# Simple-Charger-LiIon-OpampBased-LM324-al.net
KiCad netlist of a schematic drawn in EAGLE
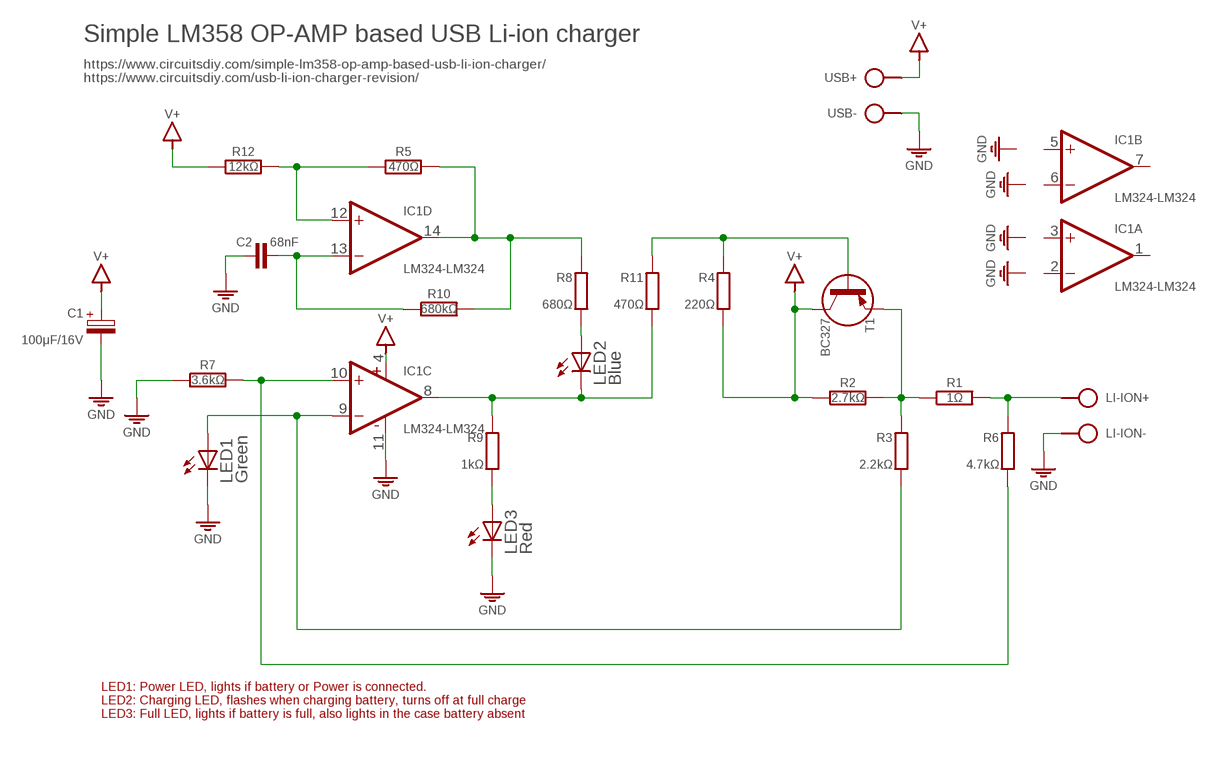
[diagram p0: schematic, sheet 1]

(export (version "E")
  (design (tool "Eeschema 10.0.6"))
  (components
    (comp (ref "C1")
      (value "100μF/16V")
      (footprint "eagle-import:E2,5-5_V")
      (libsource (lib "eagle-import") (part "CPOLE2,5-5/V"))
    )
    (comp (ref "C2")
      (value "68nF")
      (footprint "eagle-import:C050-020X044_V")
      (libsource (lib "eagle-import") (part "C-H050-020X044/V"))
    )
    (comp (ref "IC1")
      (value "LM324-LM324")
      (footprint "eagle-import:DIL14-LM324")
      (libsource (lib "eagle-import") (part "LM324-LM324"))
    )
    (comp (ref "LED1")
      (value "Green")
      (footprint "eagle-import:LED3MM")
      (libsource (lib "eagle-import") (part "LED3MM"))
    )
    (comp (ref "LED2")
      (value "Blue")
      (footprint "eagle-import:LED3MM")
      (libsource (lib "eagle-import") (part "LED3MM"))
    )
    (comp (ref "LED3")
      (value "Red")
      (footprint "eagle-import:LED3MM")
      (libsource (lib "eagle-import") (part "LED3MM"))
    )
    (comp (ref "LI-ION")
      (value "SPAD+-+-")
      (footprint "eagle-import:SPAD+-")
      (libsource (lib "eagle-import") (part "SPAD+-+-"))
    )
    (comp (ref "R1")
      (value "1Ω")
      (footprint "eagle-import:0204_10-V")
      (libsource (lib "eagle-import") (part "R-H0204/10-V"))
    )
    (comp (ref "R2")
      (value "2.7kΩ")
      (footprint "eagle-import:0204_10-V")
      (libsource (lib "eagle-import") (part "R-H0204/10-V"))
    )
    (comp (ref "R3")
      (value "2.2kΩ")
      (footprint "eagle-import:0204_10-V")
      (libsource (lib "eagle-import") (part "R0204/10-V"))
    )
    (comp (ref "R4")
      (value "220Ω")
      (footprint "eagle-import:0204_10")
      (libsource (lib "eagle-import") (part "R0204/10"))
    )
    (comp (ref "R5")
      (value "470Ω")
      (footprint "eagle-import:0204_10")
      (libsource (lib "eagle-import") (part "R-H0204/10"))
    )
    (comp (ref "R6")
      (value "4.7kΩ")
      (footprint "eagle-import:0204_10-V")
      (libsource (lib "eagle-import") (part "R0204/10-V"))
    )
    (comp (ref "R7")
      (value "3.6kΩ")
      (footprint "eagle-import:0204_12-V")
      (libsource (lib "eagle-import") (part "R-H0204/12-V"))
    )
    (comp (ref "R8")
      (value "680Ω")
      (footprint "eagle-import:0204_10")
      (libsource (lib "eagle-import") (part "R0204/10"))
    )
    (comp (ref "R9")
      (value "1kΩ")
      (footprint "eagle-import:0204_10-V")
      (libsource (lib "eagle-import") (part "R0204/10-V"))
    )
    (comp (ref "R10")
      (value "680kΩ")
      (footprint "eagle-import:0204_2V")
      (libsource (lib "eagle-import") (part "R-H0204/2V"))
    )
    (comp (ref "R11")
      (value "470Ω")
      (footprint "eagle-import:0204_10-V")
      (libsource (lib "eagle-import") (part "R0204/10-V"))
    )
    (comp (ref "R12")
      (value "12kΩ")
      (footprint "eagle-import:0204_10-V")
      (libsource (lib "eagle-import") (part "R-H0204/10-V"))
    )
    (comp (ref "T1")
      (value "BC327")
      (footprint "eagle-import:TO92")
      (libsource (lib "eagle-import") (part "BC327"))
    )
    (comp (ref "USB")
      (value "SPAD+--+")
      (footprint "eagle-import:SPAD-+")
      (libsource (lib "eagle-import") (part "SPAD+--+"))
    )
  )
  (nets
    (net (code "1") (name "GND") (class "Default")
      (node (ref "C1") (pin "-") (pinfunction "-_-") (pintype "passive"))
      (node (ref "C2") (pin "1") (pinfunction "1_1") (pintype "passive"))
      (node (ref "IC1") (pin "11") (pinfunction "V-_11") (pintype "power_in"))
      (node (ref "LED1") (pin "K") (pinfunction "C_K") (pintype "passive"))
      (node (ref "LED3") (pin "K") (pinfunction "C_K") (pintype "passive"))
      (node (ref "LI-ION") (pin "1") (pinfunction "P$1_1") (pintype "passive"))
      (node (ref "R7") (pin "1") (pinfunction "1_1") (pintype "passive"))
      (node (ref "USB") (pin "1") (pinfunction "P$1_1") (pintype "passive"))
    )
    (net (code "2") (name "Net-(IC1C-+IN)") (class "Default")
      (node (ref "IC1") (pin "10") (pinfunction "+IN_10") (pintype "input"))
      (node (ref "R6") (pin "2") (pinfunction "2_2") (pintype "passive"))
      (node (ref "R7") (pin "2") (pinfunction "2_2") (pintype "passive"))
    )
    (net (code "3") (name "Net-(IC1C--IN)") (class "Default")
      (node (ref "IC1") (pin "9") (pinfunction "-IN_9") (pintype "input"))
      (node (ref "LED1") (pin "A") (pinfunction "A_A") (pintype "passive"))
      (node (ref "R3") (pin "2") (pinfunction "2_2") (pintype "passive"))
    )
    (net (code "4") (name "Net-(IC1C-OUT)") (class "Default")
      (node (ref "IC1") (pin "8") (pinfunction "OUT_8") (pintype "output"))
      (node (ref "LED2") (pin "K") (pinfunction "C_K") (pintype "passive"))
      (node (ref "R11") (pin "2") (pinfunction "2_2") (pintype "passive"))
      (node (ref "R9") (pin "1") (pinfunction "1_1") (pintype "passive"))
    )
    (net (code "5") (name "Net-(IC1D-+IN)") (class "Default")
      (node (ref "IC1") (pin "12") (pinfunction "+IN_12") (pintype "input"))
      (node (ref "R12") (pin "2") (pinfunction "2_2") (pintype "passive"))
      (node (ref "R5") (pin "1") (pinfunction "1_1") (pintype "passive"))
    )
    (net (code "6") (name "Net-(IC1D--IN)") (class "Default")
      (node (ref "C2") (pin "2") (pinfunction "2_2") (pintype "passive"))
      (node (ref "IC1") (pin "13") (pinfunction "-IN_13") (pintype "input"))
      (node (ref "R10") (pin "1") (pinfunction "1_1") (pintype "passive"))
    )
    (net (code "7") (name "Net-(IC1D-OUT)") (class "Default")
      (node (ref "IC1") (pin "14") (pinfunction "OUT_14") (pintype "output"))
      (node (ref "R10") (pin "2") (pinfunction "2_2") (pintype "passive"))
      (node (ref "R5") (pin "2") (pinfunction "2_2") (pintype "passive"))
      (node (ref "R8") (pin "1") (pinfunction "1_1") (pintype "passive"))
    )
    (net (code "8") (name "Net-(LED2-PadA)") (class "Default")
      (node (ref "LED2") (pin "A") (pinfunction "A_A") (pintype "passive"))
      (node (ref "R8") (pin "2") (pinfunction "2_2") (pintype "passive"))
    )
    (net (code "9") (name "Net-(LED3-PadA)") (class "Default")
      (node (ref "LED3") (pin "A") (pinfunction "A_A") (pintype "passive"))
      (node (ref "R9") (pin "2") (pinfunction "2_2") (pintype "passive"))
    )
    (net (code "10") (name "Net-(LI-IONA-P$1)") (class "Default")
      (node (ref "LI-ION") (pin "2") (pinfunction "P$1_2") (pintype "passive"))
      (node (ref "R1") (pin "2") (pinfunction "2_2") (pintype "passive"))
      (node (ref "R6") (pin "1") (pinfunction "1_1") (pintype "passive"))
    )
    (net (code "11") (name "Net-(T1-B)") (class "Default")
      (node (ref "R11") (pin "1") (pinfunction "1_1") (pintype "passive"))
      (node (ref "R4") (pin "1") (pinfunction "1_1") (pintype "passive"))
      (node (ref "T1") (pin "2") (pinfunction "B_2") (pintype "passive"))
    )
    (net (code "12") (name "Net-(T1-E)") (class "Default")
      (node (ref "R1") (pin "1") (pinfunction "1_1") (pintype "passive"))
      (node (ref "R2") (pin "2") (pinfunction "2_2") (pintype "passive"))
      (node (ref "R3") (pin "1") (pinfunction "1_1") (pintype "passive"))
      (node (ref "T1") (pin "3") (pinfunction "E_3") (pintype "passive"))
    )
    (net (code "13") (name "V+") (class "Default")
      (node (ref "C1") (pin "+") (pinfunction "+_+") (pintype "passive"))
      (node (ref "IC1") (pin "4") (pinfunction "V+_4") (pintype "power_in"))
      (node (ref "R12") (pin "1") (pinfunction "1_1") (pintype "passive"))
      (node (ref "R2") (pin "1") (pinfunction "1_1") (pintype "passive"))
      (node (ref "R4") (pin "2") (pinfunction "2_2") (pintype "passive"))
      (node (ref "T1") (pin "1") (pinfunction "C_1") (pintype "passive"))
      (node (ref "USB") (pin "2") (pinfunction "P$1_2") (pintype "passive"))
    )
    (net (code "14") (name "unconnected-(IC1A-+IN-Pad3)") (class "Default")
      (node (ref "IC1") (pin "3") (pinfunction "+IN_3") (pintype "input"))
    )
    (net (code "15") (name "unconnected-(IC1A--IN-Pad2)") (class "Default")
      (node (ref "IC1") (pin "2") (pinfunction "-IN_2") (pintype "input"))
    )
    (net (code "16") (name "unconnected-(IC1A-OUT-Pad1)") (class "Default")
      (node (ref "IC1") (pin "1") (pinfunction "OUT_1") (pintype "output"))
    )
    (net (code "17") (name "unconnected-(IC1B-+IN-Pad5)") (class "Default")
      (node (ref "IC1") (pin "5") (pinfunction "+IN_5") (pintype "input"))
    )
    (net (code "18") (name "unconnected-(IC1B--IN-Pad6)") (class "Default")
      (node (ref "IC1") (pin "6") (pinfunction "-IN_6") (pintype "input"))
    )
    (net (code "19") (name "unconnected-(IC1B-OUT-Pad7)") (class "Default")
      (node (ref "IC1") (pin "7") (pinfunction "OUT_7") (pintype "output"))
    )
  )
)
